# IRcamera.net
KiCad netlist of a schematic drawn in EAGLE
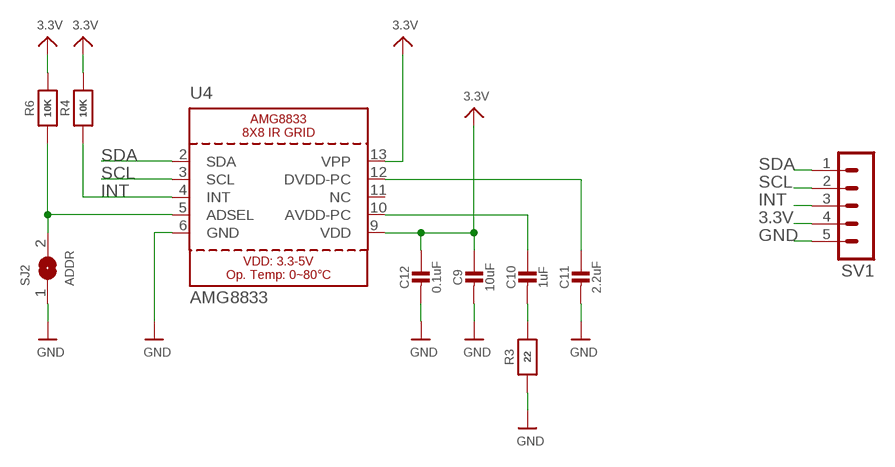
[diagram p0: schematic, sheet 1]

(export (version "E")
  (design (tool "Eeschema 10.0.6"))
  (components
    (comp (ref "C9")
      (value "10uF")
      (footprint "eagle-import:0805-NO")
      (libsource (lib "eagle-import") (part "CAP_CERAMIC0805-NOOUTLINE"))
    )
    (comp (ref "C10")
      (value "1uF")
      (footprint "eagle-import:0805-NO")
      (libsource (lib "eagle-import") (part "CAP_CERAMIC0805-NOOUTLINE"))
    )
    (comp (ref "C11")
      (value "2.2uF")
      (footprint "eagle-import:0805-NO")
      (libsource (lib "eagle-import") (part "CAP_CERAMIC0805-NOOUTLINE"))
    )
    (comp (ref "C12")
      (value "0.1uF")
      (footprint "eagle-import:0805-NO")
      (libsource (lib "eagle-import") (part "CAP_CERAMIC0805-NOOUTLINE"))
    )
    (comp (ref "R3")
      (value "22")
      (footprint "eagle-import:0805-NO")
      (libsource (lib "eagle-import") (part "RESISTOR0805_NOOUTLINE"))
    )
    (comp (ref "R4")
      (value "10K")
      (footprint "eagle-import:0805-NO")
      (libsource (lib "eagle-import") (part "RESISTOR0805_NOOUTLINE"))
    )
    (comp (ref "R6")
      (value "10K")
      (footprint "eagle-import:0805-NO")
      (libsource (lib "eagle-import") (part "RESISTOR0805_NOOUTLINE"))
    )
    (comp (ref "SJ2")
      (value "ADDR")
      (footprint "eagle-import:SOLDERJUMPER_ARROW_NOPASTE")
      (libsource (lib "eagle-import") (part "SOLDERJUMPER"))
    )
    (comp (ref "SV1")
      (value "MA05-1")
      (footprint "eagle-import:MA05-1")
      (libsource (lib "eagle-import") (part "MA05-1"))
    )
    (comp (ref "U4")
      (value "AMG8833")
      (footprint "eagle-import:AMG8833")
      (libsource (lib "eagle-import") (part "AMG8833"))
    )
  )
  (nets
    (net (code "1") (name "/INT") (class "Default")
      (node (ref "R4") (pin "1") (pinfunction "1_1") (pintype "passive"))
      (node (ref "SV1") (pin "3") (pinfunction "3_3") (pintype "passive"))
      (node (ref "U4") (pin "4") (pinfunction "INT_4") (pintype "output"))
    )
    (net (code "2") (name "/SCL") (class "Default")
      (node (ref "SV1") (pin "2") (pinfunction "2_2") (pintype "passive"))
      (node (ref "U4") (pin "3") (pinfunction "SCL_3") (pintype "bidirectional"))
    )
    (net (code "3") (name "/SDA") (class "Default")
      (node (ref "SV1") (pin "1") (pinfunction "1_1") (pintype "passive"))
      (node (ref "U4") (pin "2") (pinfunction "SDA_2") (pintype "bidirectional"))
    )
    (net (code "4") (name "3.3V") (class "Default")
      (node (ref "C12") (pin "1") (pinfunction "1_1") (pintype "passive"))
      (node (ref "C9") (pin "1") (pinfunction "1_1") (pintype "passive"))
      (node (ref "R4") (pin "2") (pinfunction "2_2") (pintype "passive"))
      (node (ref "R6") (pin "2") (pinfunction "2_2") (pintype "passive"))
      (node (ref "SV1") (pin "4") (pinfunction "4_4") (pintype "passive"))
      (node (ref "U4") (pin "13") (pinfunction "VPP_13") (pintype "power_in"))
      (node (ref "U4") (pin "9") (pinfunction "VDD_9") (pintype "power_in"))
    )
    (net (code "5") (name "GND") (class "Default")
      (node (ref "C11") (pin "2") (pinfunction "2_2") (pintype "passive"))
      (node (ref "C12") (pin "2") (pinfunction "2_2") (pintype "passive"))
      (node (ref "C9") (pin "2") (pinfunction "2_2") (pintype "passive"))
      (node (ref "R3") (pin "1") (pinfunction "1_1") (pintype "passive"))
      (node (ref "SJ2") (pin "1") (pinfunction "1_1") (pintype "passive"))
      (node (ref "SV1") (pin "5") (pinfunction "5_5") (pintype "passive"))
      (node (ref "U4") (pin "6") (pinfunction "GND_6") (pintype "power_in"))
    )
    (net (code "6") (name "Net-(C10-Pad2)") (class "Default")
      (node (ref "C10") (pin "2") (pinfunction "2_2") (pintype "passive"))
      (node (ref "R3") (pin "2") (pinfunction "2_2") (pintype "passive"))
    )
    (net (code "7") (name "Net-(U4-ADSEL)") (class "Default")
      (node (ref "R6") (pin "1") (pinfunction "1_1") (pintype "passive"))
      (node (ref "SJ2") (pin "2") (pinfunction "2_2") (pintype "passive"))
      (node (ref "U4") (pin "5") (pinfunction "ADSEL_5") (pintype "input"))
    )
    (net (code "8") (name "Net-(U4-AVDD-PC)") (class "Default")
      (node (ref "C10") (pin "1") (pinfunction "1_1") (pintype "passive"))
      (node (ref "U4") (pin "10") (pinfunction "AVDD-PC_10") (pintype "power_in"))
    )
    (net (code "9") (name "Net-(U4-DVDD-PC)") (class "Default")
      (node (ref "C11") (pin "1") (pinfunction "1_1") (pintype "passive"))
      (node (ref "U4") (pin "12") (pinfunction "DVDD-PC_12") (pintype "power_in"))
    )
    (net (code "10") (name "unconnected-(U4-NC-Pad11)") (class "Default")
      (node (ref "U4") (pin "11") (pinfunction "NC_11") (pintype "bidirectional"))
    )
  )
)
